# Sheet3.net
KiCad netlist of a schematic drawn in Altium Designer
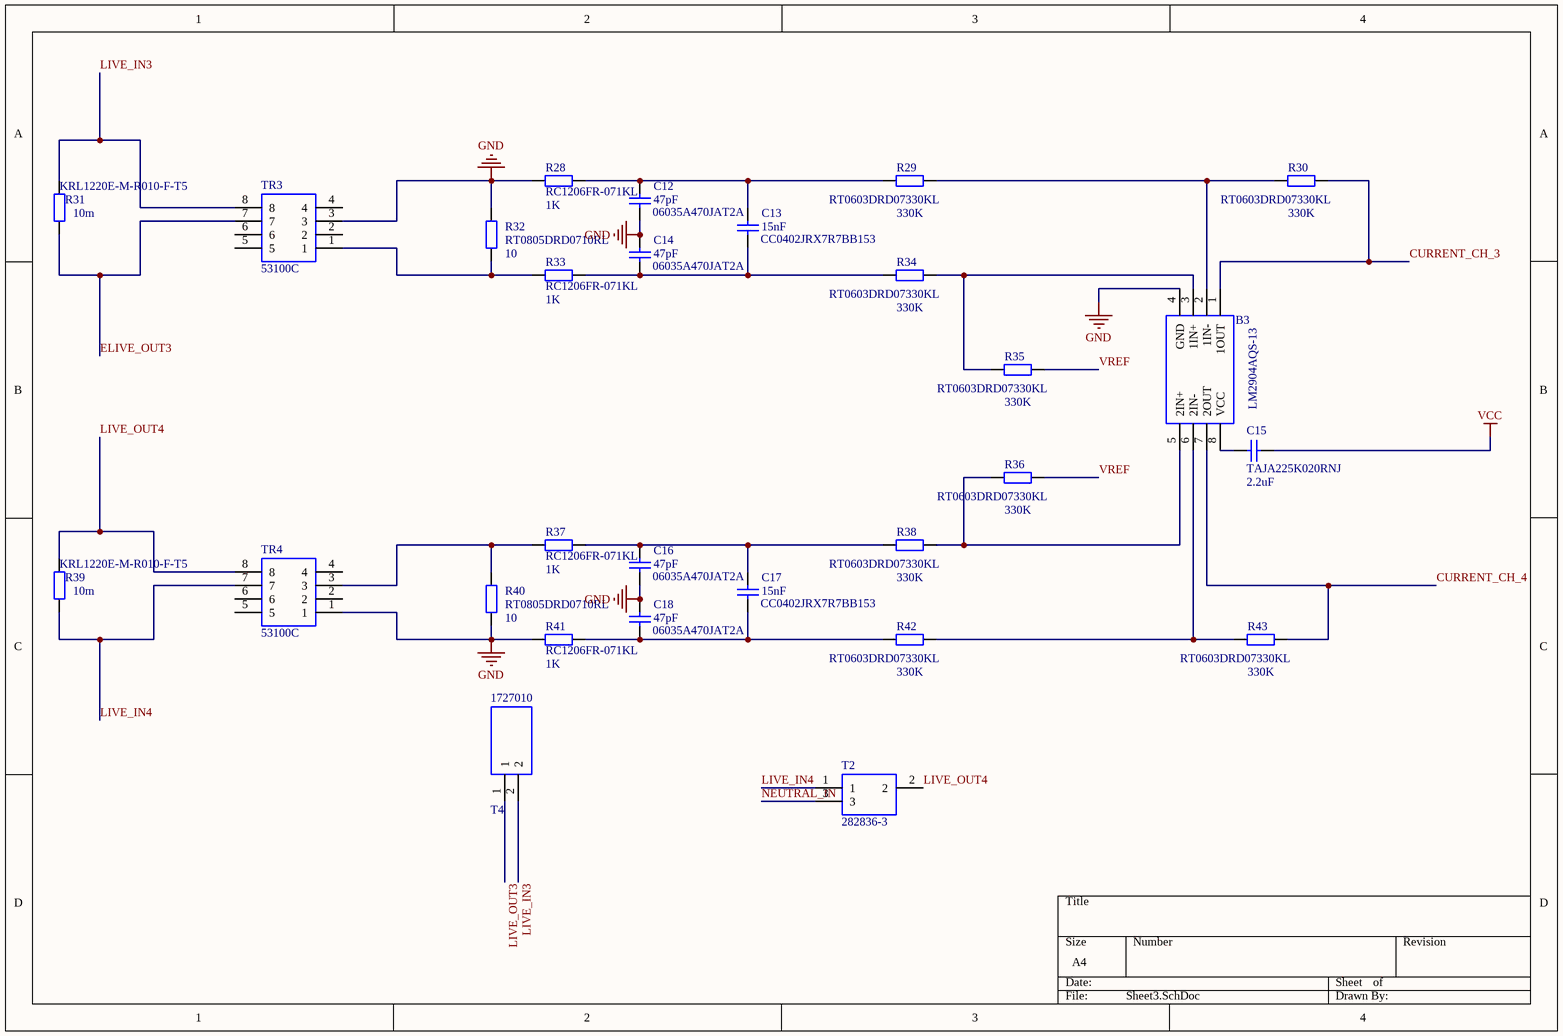
[diagram p0: Sheet3.SchDoc]

(export (version "E")
  (design (tool "Eeschema 10.0.6"))
  (components
    (comp (ref "B3")
      (value "LM2904AQS-13")
      (footprint "SOIC127P600X175-8N:SOIC127P600X175-8N")
      (description "https://www.diodes.com/assets/Datasheets/LM2902_04.pdf")
      (fields (field (name "MANUFACTURER_PART_NUMBER") "LM2904AS-13"))
      (libsource (lib "LM2904AS-13") (part "LM2904AS-13"))
    )
    (comp (ref "C12")
      (value "06035A470JAT2A")
      (footprint "AltiumDesigner:0603-M")
      (description "Capacitor")
      (fields (field (name "ALTIUM_VALUE") "47pF") (field (name "PUBLISHER") "Altium Limited"))
      (libsource (lib "Miscellaneous Devices") (part "Cap"))
    )
    (comp (ref "C13")
      (value "CC0402JRX7R7BB153")
      (footprint "CAPC1005X55N:CAPC1005X55N")
      (description "Capacitor")
      (fields (field (name "ALTIUM_VALUE") "15nF") (field (name "PUBLISHER") "Altium Limited"))
      (libsource (lib "Miscellaneous Devices") (part "Cap"))
    )
    (comp (ref "C14")
      (value "06035A470JAT2A")
      (footprint "AltiumDesigner:0603-M")
      (description "Capacitor")
      (fields (field (name "ALTIUM_VALUE") "47pF") (field (name "PUBLISHER") "Altium Limited"))
      (libsource (lib "Miscellaneous Devices") (part "Cap"))
    )
    (comp (ref "C15")
      (value "TAJA225K020RNJ")
      (footprint "CAPPM3216X180N:CAPPM3216X180N")
      (description "Capacitor")
      (fields (field (name "ALTIUM_VALUE") "2.2uF") (field (name "PUBLISHER") "Altium Limited"))
      (libsource (lib "Miscellaneous Devices") (part "Cap"))
    )
    (comp (ref "C16")
      (value "06035A470JAT2A")
      (footprint "AltiumDesigner:0603-M")
      (description "Capacitor")
      (fields (field (name "ALTIUM_VALUE") "47pF") (field (name "PUBLISHER") "Altium Limited"))
      (libsource (lib "Miscellaneous Devices") (part "Cap"))
    )
    (comp (ref "C17")
      (value "CC0402JRX7R7BB153")
      (footprint "CAPC1005X55N:CAPC1005X55N")
      (description "Capacitor")
      (fields (field (name "ALTIUM_VALUE") "15nF") (field (name "PUBLISHER") "Altium Limited"))
      (libsource (lib "Miscellaneous Devices") (part "Cap"))
    )
    (comp (ref "C18")
      (value "06035A470JAT2A")
      (footprint "AltiumDesigner:0603-M")
      (description "Capacitor")
      (fields (field (name "ALTIUM_VALUE") "47pF") (field (name "PUBLISHER") "Altium Limited"))
      (libsource (lib "Miscellaneous Devices") (part "Cap"))
    )
    (comp (ref "R28")
      (value "RC1206FR-071KL")
      (footprint "AltiumDesigner:RC1206N-M")
      (description "Resistor")
      (fields (field (name "ALTIUM_VALUE") "1K") (field (name "PUBLISHER") "Altium Limited"))
      (libsource (lib "") (part "Res2_1"))
    )
    (comp (ref "R29")
      (value "RT0603DRD07330KL")
      (footprint "AltiumDesigner:RC0603N-M")
      (description "Resistor")
      (fields (field (name "ALTIUM_VALUE") "330K") (field (name "PUBLISHER") "Altium Limited"))
      (libsource (lib "Miscellaneous Devices") (part "Res2"))
    )
    (comp (ref "R30")
      (value "RT0603DRD07330KL")
      (footprint "AltiumDesigner:RC0603N-M")
      (description "Resistor")
      (fields (field (name "ALTIUM_VALUE") "330K") (field (name "PUBLISHER") "Altium Limited"))
      (libsource (lib "Miscellaneous Devices") (part "Res2"))
    )
    (comp (ref "R31")
      (value "KRL1220E-M-R010-F-T5")
      (footprint "AltiumDesigner:RES_1220-M")
      (description "Resistor")
      (fields (field (name "ALTIUM_VALUE") "10m") (field (name "PUBLISHER") "Altium Limited"))
      (libsource (lib "") (part "Res2_2"))
    )
    (comp (ref "R32")
      (value "RT0805DRD0710RL")
      (footprint "AltiumDesigner:RC0805N-M")
      (description "Resistor")
      (fields (field (name "ALTIUM_VALUE") "10") (field (name "PUBLISHER") "Altium Limited"))
      (libsource (lib "") (part "Res2_2"))
    )
    (comp (ref "R33")
      (value "RC1206FR-071KL")
      (footprint "AltiumDesigner:RC1206N-M")
      (description "Resistor")
      (fields (field (name "ALTIUM_VALUE") "1K") (field (name "PUBLISHER") "Altium Limited"))
      (libsource (lib "") (part "Res2_1"))
    )
    (comp (ref "R34")
      (value "RT0603DRD07330KL")
      (footprint "AltiumDesigner:RC0603N-M")
      (description "Resistor")
      (fields (field (name "ALTIUM_VALUE") "330K") (field (name "PUBLISHER") "Altium Limited"))
      (libsource (lib "Miscellaneous Devices") (part "Res2"))
    )
    (comp (ref "R35")
      (value "RT0603DRD07330KL")
      (footprint "AltiumDesigner:RC0603N-M")
      (description "Resistor")
      (fields (field (name "ALTIUM_VALUE") "330K") (field (name "PUBLISHER") "Altium Limited"))
      (libsource (lib "Miscellaneous Devices") (part "Res2"))
    )
    (comp (ref "R36")
      (value "RT0603DRD07330KL")
      (footprint "AltiumDesigner:RC0603N-M")
      (description "Resistor")
      (fields (field (name "ALTIUM_VALUE") "330K") (field (name "PUBLISHER") "Altium Limited"))
      (libsource (lib "Miscellaneous Devices") (part "Res2"))
    )
    (comp (ref "R37")
      (value "RC1206FR-071KL")
      (footprint "AltiumDesigner:RC1206N-M")
      (description "Resistor")
      (fields (field (name "ALTIUM_VALUE") "1K") (field (name "PUBLISHER") "Altium Limited"))
      (libsource (lib "") (part "Res2_1"))
    )
    (comp (ref "R38")
      (value "RT0603DRD07330KL")
      (footprint "AltiumDesigner:RC0603N-M")
      (description "Resistor")
      (fields (field (name "ALTIUM_VALUE") "330K") (field (name "PUBLISHER") "Altium Limited"))
      (libsource (lib "Miscellaneous Devices") (part "Res2"))
    )
    (comp (ref "R39")
      (value "KRL1220E-M-R010-F-T5")
      (footprint "AltiumDesigner:RES_1220-M")
      (description "Resistor")
      (fields (field (name "ALTIUM_VALUE") "10m") (field (name "PUBLISHER") "Altium Limited"))
      (libsource (lib "") (part "Res2_2"))
    )
    (comp (ref "R40")
      (value "RT0805DRD0710RL")
      (footprint "AltiumDesigner:RC0805N-M")
      (description "Resistor")
      (fields (field (name "ALTIUM_VALUE") "10") (field (name "PUBLISHER") "Altium Limited"))
      (libsource (lib "") (part "Res2_2"))
    )
    (comp (ref "R41")
      (value "RC1206FR-071KL")
      (footprint "AltiumDesigner:RC1206N-M")
      (description "Resistor")
      (fields (field (name "ALTIUM_VALUE") "1K") (field (name "PUBLISHER") "Altium Limited"))
      (libsource (lib "") (part "Res2_1"))
    )
    (comp (ref "R42")
      (value "RT0603DRD07330KL")
      (footprint "AltiumDesigner:RC0603N-M")
      (description "Resistor")
      (fields (field (name "ALTIUM_VALUE") "330K") (field (name "PUBLISHER") "Altium Limited"))
      (libsource (lib "Miscellaneous Devices") (part "Res2"))
    )
    (comp (ref "R43")
      (value "RT0603DRD07330KL")
      (footprint "AltiumDesigner:RC0603N-M")
      (description "Resistor")
      (fields (field (name "ALTIUM_VALUE") "330K") (field (name "PUBLISHER") "Altium Limited"))
      (libsource (lib "Miscellaneous Devices") (part "Res2"))
    )
    (comp (ref "T2")
      (value "282836-3")
      (footprint "282836-3:282836-3")
      (description "3 way PCB screw terminal,5mm pitch")
      (fields (field (name "RS PART NUMBER") "1648600"))
      (libsource (lib "282836-3") (part "282836-3"))
    )
    (comp (ref "T4")
      (value "1727010")
      (footprint "SHDR2W90P0X350_1X2_750X730X850:SHDR2W90P0X350_1X2_750X730X850P")
      (fields (field (name "RS PART NUMBER") "1015384"))
      (libsource (lib "1727010") (part "1727010"))
    )
    (comp (ref "TR3")
      (value "53100C")
      (footprint "53050C:53050C")
      (fields (field (name "RS PART NUMBER") "7157021P") (field (name "MANUFACTURER_PART_NUMBER") "53050C"))
      (libsource (lib "53050C") (part "53050C"))
    )
    (comp (ref "TR4")
      (value "53100C")
      (footprint "53050C:53050C")
      (fields (field (name "RS PART NUMBER") "7157021P") (field (name "MANUFACTURER_PART_NUMBER") "53050C"))
      (libsource (lib "53050C") (part "53050C"))
    )
  )
  (nets
    (net (code "1") (name "/CURRENT_CH_3") (class "Default")
      (node (ref "B3") (pin "1") (pinfunction "1OUT_1") (pintype "passive"))
      (node (ref "R30") (pin "2") (pinfunction "2_2") (pintype "passive"))
    )
    (net (code "2") (name "/CURRENT_CH_4") (class "Default")
      (node (ref "B3") (pin "7") (pinfunction "2OUT_7") (pintype "passive"))
      (node (ref "R43") (pin "2") (pinfunction "2_2") (pintype "passive"))
    )
    (net (code "3") (name "/ELIVE_OUT3") (class "Default")
      (node (ref "R31") (pin "1") (pinfunction "1_1") (pintype "passive"))
      (node (ref "TR3") (pin "7") (pinfunction "7_7") (pintype "passive"))
    )
    (net (code "4") (name "/LIVE_IN3") (class "Default")
      (node (ref "R31") (pin "2") (pinfunction "2_2") (pintype "passive"))
      (node (ref "T4") (pin "2") (pinfunction "2_2") (pintype "passive"))
      (node (ref "TR3") (pin "8") (pinfunction "8_8") (pintype "passive"))
    )
    (net (code "5") (name "/LIVE_IN4") (class "Default")
      (node (ref "R39") (pin "1") (pinfunction "1_1") (pintype "passive"))
      (node (ref "T2") (pin "1") (pinfunction "1_1") (pintype "passive"))
      (node (ref "TR4") (pin "7") (pinfunction "7_7") (pintype "passive"))
    )
    (net (code "6") (name "/LIVE_OUT3") (class "Default")
      (node (ref "T4") (pin "1") (pinfunction "1_1") (pintype "passive"))
    )
    (net (code "7") (name "/LIVE_OUT4") (class "Default")
      (node (ref "R39") (pin "2") (pinfunction "2_2") (pintype "passive"))
      (node (ref "T2") (pin "2") (pinfunction "2_2") (pintype "passive"))
      (node (ref "TR4") (pin "8") (pinfunction "8_8") (pintype "passive"))
    )
    (net (code "8") (name "/NEUTRAL_IN") (class "Default")
      (node (ref "T2") (pin "3") (pinfunction "3_3") (pintype "passive"))
    )
    (net (code "9") (name "/VREF") (class "Default")
      (node (ref "R35") (pin "2") (pinfunction "2_2") (pintype "passive"))
      (node (ref "R36") (pin "2") (pinfunction "2_2") (pintype "passive"))
    )
    (net (code "10") (name "GND") (class "Default")
      (node (ref "B3") (pin "4") (pinfunction "GND_4") (pintype "passive"))
      (node (ref "C12") (pin "1") (pinfunction "1_1") (pintype "passive"))
      (node (ref "C14") (pin "2") (pinfunction "2_2") (pintype "passive"))
      (node (ref "C16") (pin "1") (pinfunction "1_1") (pintype "passive"))
      (node (ref "C18") (pin "2") (pinfunction "2_2") (pintype "passive"))
      (node (ref "R28") (pin "2") (pinfunction "2_2") (pintype "passive"))
      (node (ref "R32") (pin "2") (pinfunction "2_2") (pintype "passive"))
      (node (ref "R40") (pin "1") (pinfunction "1_1") (pintype "passive"))
      (node (ref "R41") (pin "2") (pinfunction "2_2") (pintype "passive"))
      (node (ref "TR3") (pin "3") (pinfunction "3_3") (pintype "passive"))
      (node (ref "TR4") (pin "1") (pinfunction "1_1") (pintype "passive"))
    )
    (net (code "11") (name "Net-(B3-1IN+)") (class "Default")
      (node (ref "B3") (pin "3") (pinfunction "1IN+_3") (pintype "passive"))
      (node (ref "R34") (pin "2") (pinfunction "2_2") (pintype "passive"))
      (node (ref "R35") (pin "1") (pinfunction "1_1") (pintype "passive"))
    )
    (net (code "12") (name "Net-(B3-1IN-)") (class "Default")
      (node (ref "B3") (pin "2") (pinfunction "1IN-_2") (pintype "passive"))
      (node (ref "R29") (pin "2") (pinfunction "2_2") (pintype "passive"))
      (node (ref "R30") (pin "1") (pinfunction "1_1") (pintype "passive"))
    )
    (net (code "13") (name "Net-(B3-2IN+)") (class "Default")
      (node (ref "B3") (pin "5") (pinfunction "2IN+_5") (pintype "passive"))
      (node (ref "R36") (pin "1") (pinfunction "1_1") (pintype "passive"))
      (node (ref "R38") (pin "2") (pinfunction "2_2") (pintype "passive"))
    )
    (net (code "14") (name "Net-(B3-2IN-)") (class "Default")
      (node (ref "B3") (pin "6") (pinfunction "2IN-_6") (pintype "passive"))
      (node (ref "R42") (pin "2") (pinfunction "2_2") (pintype "passive"))
      (node (ref "R43") (pin "1") (pinfunction "1_1") (pintype "passive"))
    )
    (net (code "15") (name "Net-(B3-VCC)") (class "Default")
      (node (ref "B3") (pin "8") (pinfunction "VCC_8") (pintype "power_in"))
      (node (ref "C15") (pin "2") (pinfunction "2_2") (pintype "passive"))
    )
    (net (code "16") (name "Net-(C12-Pad2)") (class "Default")
      (node (ref "C12") (pin "2") (pinfunction "2_2") (pintype "passive"))
      (node (ref "C13") (pin "2") (pinfunction "2_2") (pintype "passive"))
      (node (ref "R28") (pin "1") (pinfunction "1_1") (pintype "passive"))
      (node (ref "R29") (pin "1") (pinfunction "1_1") (pintype "passive"))
    )
    (net (code "17") (name "Net-(C13-Pad1)") (class "Default")
      (node (ref "C13") (pin "1") (pinfunction "1_1") (pintype "passive"))
      (node (ref "C14") (pin "1") (pinfunction "1_1") (pintype "passive"))
      (node (ref "R33") (pin "1") (pinfunction "1_1") (pintype "passive"))
      (node (ref "R34") (pin "1") (pinfunction "1_1") (pintype "passive"))
    )
    (net (code "18") (name "Net-(C16-Pad2)") (class "Default")
      (node (ref "C16") (pin "2") (pinfunction "2_2") (pintype "passive"))
      (node (ref "C17") (pin "2") (pinfunction "2_2") (pintype "passive"))
      (node (ref "R37") (pin "1") (pinfunction "1_1") (pintype "passive"))
      (node (ref "R38") (pin "1") (pinfunction "1_1") (pintype "passive"))
    )
    (net (code "19") (name "Net-(C17-Pad1)") (class "Default")
      (node (ref "C17") (pin "1") (pinfunction "1_1") (pintype "passive"))
      (node (ref "C18") (pin "1") (pinfunction "1_1") (pintype "passive"))
      (node (ref "R41") (pin "1") (pinfunction "1_1") (pintype "passive"))
      (node (ref "R42") (pin "1") (pinfunction "1_1") (pintype "passive"))
    )
    (net (code "20") (name "Net-(R32-Pad1)") (class "Default")
      (node (ref "R32") (pin "1") (pinfunction "1_1") (pintype "passive"))
      (node (ref "R33") (pin "2") (pinfunction "2_2") (pintype "passive"))
      (node (ref "TR3") (pin "1") (pinfunction "1_1") (pintype "passive"))
    )
    (net (code "21") (name "Net-(R37-Pad2)") (class "Default")
      (node (ref "R37") (pin "2") (pinfunction "2_2") (pintype "passive"))
      (node (ref "R40") (pin "2") (pinfunction "2_2") (pintype "passive"))
      (node (ref "TR4") (pin "3") (pinfunction "3_3") (pintype "passive"))
    )
    (net (code "22") (name "VCC") (class "Default")
      (node (ref "C15") (pin "1") (pinfunction "1_1") (pintype "passive"))
    )
    (net (code "23") (name "unconnected-(TR3-Pad2)") (class "Default")
      (node (ref "TR3") (pin "2") (pinfunction "2_2") (pintype "passive"))
    )
    (net (code "24") (name "unconnected-(TR3-Pad4)") (class "Default")
      (node (ref "TR3") (pin "4") (pinfunction "4_4") (pintype "passive"))
    )
    (net (code "25") (name "unconnected-(TR3-Pad5)") (class "Default")
      (node (ref "TR3") (pin "5") (pinfunction "5_5") (pintype "passive"))
    )
    (net (code "26") (name "unconnected-(TR3-Pad6)") (class "Default")
      (node (ref "TR3") (pin "6") (pinfunction "6_6") (pintype "passive"))
    )
    (net (code "27") (name "unconnected-(TR4-Pad2)") (class "Default")
      (node (ref "TR4") (pin "2") (pinfunction "2_2") (pintype "passive"))
    )
    (net (code "28") (name "unconnected-(TR4-Pad4)") (class "Default")
      (node (ref "TR4") (pin "4") (pinfunction "4_4") (pintype "passive"))
    )
    (net (code "29") (name "unconnected-(TR4-Pad5)") (class "Default")
      (node (ref "TR4") (pin "5") (pinfunction "5_5") (pintype "passive"))
    )
    (net (code "30") (name "unconnected-(TR4-Pad6)") (class "Default")
      (node (ref "TR4") (pin "6") (pinfunction "6_6") (pintype "passive"))
    )
  )
)
